# PIC32_Circuit.net
KiCad netlist of a schematic drawn in EAGLE
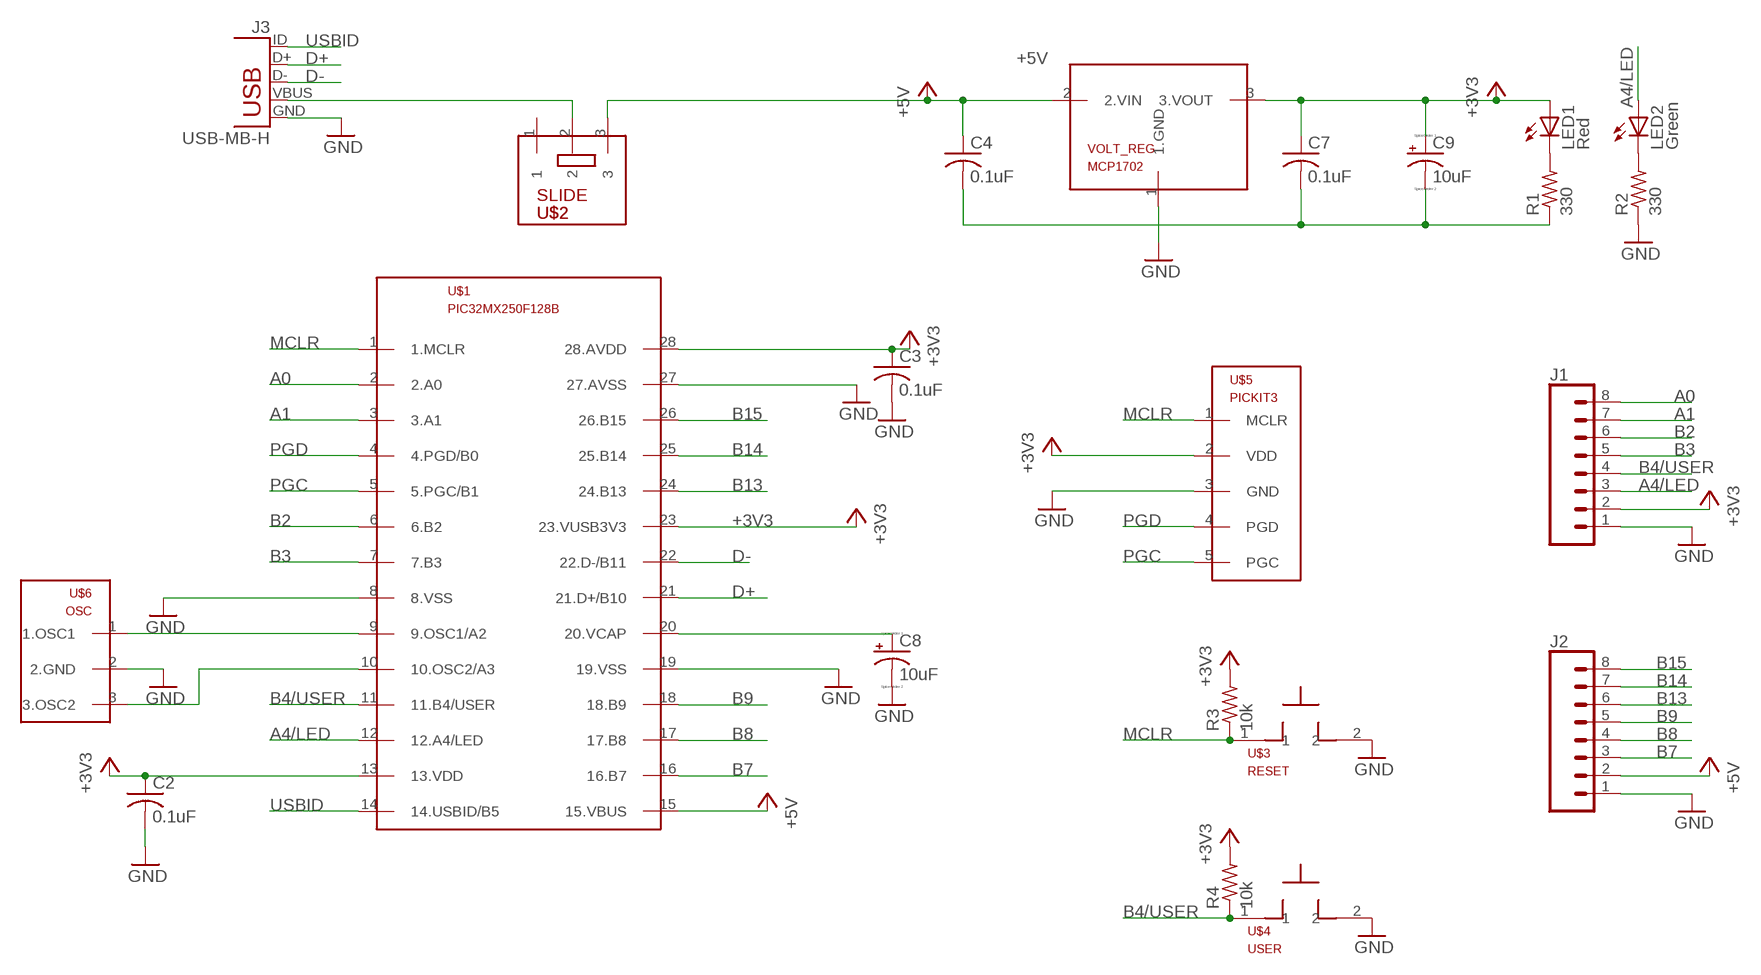
[diagram p0: schematic, sheet 1]

(export (version "E")
  (design (tool "Eeschema 10.0.6"))
  (components
    (comp (ref "C2")
      (value "0.1uF")
      (footprint "eagle-import:C025-050X050")
      (libsource (lib "eagle-import") (part "C-US025-050X050"))
    )
    (comp (ref "C3")
      (value "0.1uF")
      (footprint "eagle-import:C025-050X050")
      (libsource (lib "eagle-import") (part "C-US025-050X050"))
    )
    (comp (ref "C4")
      (value "0.1uF")
      (footprint "eagle-import:C025-050X050")
      (libsource (lib "eagle-import") (part "C-US025-050X050"))
    )
    (comp (ref "C7")
      (value "0.1uF")
      (footprint "eagle-import:C025-050X050")
      (libsource (lib "eagle-import") (part "C-US025-050X050"))
    )
    (comp (ref "C8")
      (value "10uF")
      (footprint "eagle-import:B45181B")
      (libsource (lib "eagle-import") (part "CPOL-USB45181B"))
    )
    (comp (ref "C9")
      (value "10uF")
      (footprint "eagle-import:B45181B")
      (libsource (lib "eagle-import") (part "CPOL-USB45181B"))
    )
    (comp (ref "J1")
      (value "CONN_08\"")
      (footprint "eagle-import:1X08")
      (libsource (lib "eagle-import") (part "CONN_08{dblquote}"))
    )
    (comp (ref "J2")
      (value "CONN_08\"")
      (footprint "eagle-import:1X08")
      (libsource (lib "eagle-import") (part "CONN_08{dblquote}"))
    )
    (comp (ref "J3")
      (value "USB-MB-H")
      (footprint "eagle-import:USB-MB-H")
      (libsource (lib "eagle-import") (part "USB-MB-H"))
    )
    (comp (ref "LED1")
      (value "Red")
      (footprint "eagle-import:LED3MM")
      (libsource (lib "eagle-import") (part "led_LED3MM"))
    )
    (comp (ref "LED2")
      (value "Green")
      (footprint "eagle-import:LED3MM")
      (libsource (lib "eagle-import") (part "LED3MM"))
    )
    (comp (ref "R1")
      (value "330")
      (footprint "eagle-import:0309_12")
      (libsource (lib "eagle-import") (part "resistor_R-US_0309/12"))
    )
    (comp (ref "R2")
      (value "330")
      (footprint "eagle-import:0207_10")
      (libsource (lib "eagle-import") (part "R-US_0207/10"))
    )
    (comp (ref "R3")
      (value "10k")
      (footprint "eagle-import:0207_10")
      (libsource (lib "eagle-import") (part "R-US_0207/10"))
    )
    (comp (ref "R4")
      (value "10k")
      (footprint "eagle-import:0207_10")
      (libsource (lib "eagle-import") (part "R-US_0207/10"))
    )
    (comp (ref "U$1")
      (value "PIC32MX250F128B")
      (footprint "eagle-import:DIL28-3")
      (libsource (lib "eagle-import") (part "PIC32MX250F128B"))
    )
    (comp (ref "U$2")
      (value "SLIDE")
      (footprint "eagle-import:SLIDE")
      (libsource (lib "eagle-import") (part "SLIDE"))
    )
    (comp (ref "U$3")
      (value "RESET")
      (footprint "eagle-import:PB")
      (libsource (lib "eagle-import") (part "PB"))
    )
    (comp (ref "U$4")
      (value "USER")
      (footprint "eagle-import:PB")
      (libsource (lib "eagle-import") (part "PB"))
    )
    (comp (ref "U$5")
      (value "PICKIT3")
      (footprint "eagle-import:1X05")
      (libsource (lib "eagle-import") (part "PICKIT3"))
    )
    (comp (ref "U$6")
      (value "OSC")
      (footprint "eagle-import:OSC")
      (libsource (lib "eagle-import") (part "OSC"))
    )
    (comp (ref "VOLT_REG")
      (value "MCP1702")
      (footprint "eagle-import:TO92")
      (libsource (lib "eagle-import") (part "MCP1702"))
    )
  )
  (nets
    (net (code "1") (name "+3V3") (class "Default")
      (node (ref "C2") (pin "1") (pinfunction "1_1") (pintype "passive"))
      (node (ref "C3") (pin "1") (pinfunction "1_1") (pintype "passive"))
      (node (ref "C7") (pin "1") (pinfunction "1_1") (pintype "passive"))
      (node (ref "C9") (pin "+") (pinfunction "+_+") (pintype "passive"))
      (node (ref "J1") (pin "2") (pinfunction "2_2") (pintype "passive"))
      (node (ref "LED1") (pin "A") (pinfunction "A_A") (pintype "passive"))
      (node (ref "R3") (pin "2") (pinfunction "2_2") (pintype "passive"))
      (node (ref "R4") (pin "2") (pinfunction "2_2") (pintype "passive"))
      (node (ref "U$1") (pin "13") (pinfunction "13.VDD_13") (pintype "bidirectional"))
      (node (ref "U$1") (pin "23") (pinfunction "23.VUSB3V3_23") (pintype "bidirectional"))
      (node (ref "U$1") (pin "28") (pinfunction "28.AVDD_28") (pintype "bidirectional"))
      (node (ref "U$5") (pin "2") (pinfunction "VDD_2") (pintype "bidirectional"))
      (node (ref "VOLT_REG") (pin "3") (pinfunction "3.VOUT_3") (pintype "bidirectional"))
    )
    (net (code "2") (name "+5V") (class "Default")
      (node (ref "C4") (pin "1") (pinfunction "1_1") (pintype "passive"))
      (node (ref "J2") (pin "2") (pinfunction "2_2") (pintype "passive"))
      (node (ref "U$1") (pin "15") (pinfunction "15.VBUS_15") (pintype "bidirectional"))
      (node (ref "U$2") (pin "3") (pinfunction "3_3") (pintype "bidirectional"))
      (node (ref "VOLT_REG") (pin "2") (pinfunction "2.VIN_2") (pintype "bidirectional"))
    )
    (net (code "3") (name "/A0") (class "Default")
      (node (ref "J1") (pin "8") (pinfunction "8_8") (pintype "passive"))
      (node (ref "U$1") (pin "2") (pinfunction "2.A0_2") (pintype "bidirectional"))
    )
    (net (code "4") (name "/A1") (class "Default")
      (node (ref "J1") (pin "7") (pinfunction "7_7") (pintype "passive"))
      (node (ref "U$1") (pin "3") (pinfunction "3.A1_3") (pintype "bidirectional"))
    )
    (net (code "5") (name "/A4{slash}LED") (class "Default")
      (node (ref "J1") (pin "3") (pinfunction "3_3") (pintype "passive"))
      (node (ref "LED2") (pin "A") (pinfunction "A_A") (pintype "passive"))
      (node (ref "U$1") (pin "12") (pinfunction "12.A4/LED_12") (pintype "bidirectional"))
    )
    (net (code "6") (name "/B2") (class "Default")
      (node (ref "J1") (pin "6") (pinfunction "6_6") (pintype "passive"))
      (node (ref "U$1") (pin "6") (pinfunction "6.B2_6") (pintype "bidirectional"))
    )
    (net (code "7") (name "/B3") (class "Default")
      (node (ref "J1") (pin "5") (pinfunction "5_5") (pintype "passive"))
      (node (ref "U$1") (pin "7") (pinfunction "7.B3_7") (pintype "bidirectional"))
    )
    (net (code "8") (name "/B4{slash}USER") (class "Default")
      (node (ref "J1") (pin "4") (pinfunction "4_4") (pintype "passive"))
      (node (ref "R4") (pin "1") (pinfunction "1_1") (pintype "passive"))
      (node (ref "U$1") (pin "11") (pinfunction "11.B4/USER_11") (pintype "bidirectional"))
      (node (ref "U$4") (pin "1") (pinfunction "1_1") (pintype "bidirectional"))
    )
    (net (code "9") (name "/B7") (class "Default")
      (node (ref "J2") (pin "3") (pinfunction "3_3") (pintype "passive"))
      (node (ref "U$1") (pin "16") (pinfunction "16.B7_16") (pintype "bidirectional"))
    )
    (net (code "10") (name "/B8") (class "Default")
      (node (ref "J2") (pin "4") (pinfunction "4_4") (pintype "passive"))
      (node (ref "U$1") (pin "17") (pinfunction "17.B8_17") (pintype "bidirectional"))
    )
    (net (code "11") (name "/B9") (class "Default")
      (node (ref "J2") (pin "5") (pinfunction "5_5") (pintype "passive"))
      (node (ref "U$1") (pin "18") (pinfunction "18.B9_18") (pintype "bidirectional"))
    )
    (net (code "12") (name "/B13") (class "Default")
      (node (ref "J2") (pin "6") (pinfunction "6_6") (pintype "passive"))
      (node (ref "U$1") (pin "24") (pinfunction "24.B13_24") (pintype "bidirectional"))
    )
    (net (code "13") (name "/B14") (class "Default")
      (node (ref "J2") (pin "7") (pinfunction "7_7") (pintype "passive"))
      (node (ref "U$1") (pin "25") (pinfunction "25.B14_25") (pintype "bidirectional"))
    )
    (net (code "14") (name "/B15") (class "Default")
      (node (ref "J2") (pin "8") (pinfunction "8_8") (pintype "passive"))
      (node (ref "U$1") (pin "26") (pinfunction "26.B15_26") (pintype "bidirectional"))
    )
    (net (code "15") (name "/D+") (class "Default")
      (node (ref "J3") (pin "D+") (pinfunction "D+_D+") (pintype "bidirectional"))
      (node (ref "U$1") (pin "21") (pinfunction "21.D+/B10_21") (pintype "bidirectional"))
    )
    (net (code "16") (name "/D-") (class "Default")
      (node (ref "J3") (pin "D-") (pinfunction "D-_D-") (pintype "bidirectional"))
      (node (ref "U$1") (pin "22") (pinfunction "22.D-/B11_22") (pintype "bidirectional"))
    )
    (net (code "17") (name "/MCLR") (class "Default")
      (node (ref "R3") (pin "1") (pinfunction "1_1") (pintype "passive"))
      (node (ref "U$1") (pin "1") (pinfunction "1.MCLR_1") (pintype "bidirectional"))
      (node (ref "U$3") (pin "1") (pinfunction "1_1") (pintype "bidirectional"))
      (node (ref "U$5") (pin "1") (pinfunction "MCLR_1") (pintype "bidirectional"))
    )
    (net (code "18") (name "/PGC") (class "Default")
      (node (ref "U$1") (pin "5") (pinfunction "5.PGC/B1_5") (pintype "bidirectional"))
      (node (ref "U$5") (pin "5") (pinfunction "PGC_5") (pintype "bidirectional"))
    )
    (net (code "19") (name "/PGD") (class "Default")
      (node (ref "U$1") (pin "4") (pinfunction "4.PGD/B0_4") (pintype "bidirectional"))
      (node (ref "U$5") (pin "4") (pinfunction "PGD_4") (pintype "bidirectional"))
    )
    (net (code "20") (name "/USBID") (class "Default")
      (node (ref "J3") (pin "ID") (pinfunction "ID_ID") (pintype "bidirectional"))
      (node (ref "U$1") (pin "14") (pinfunction "14.USBID/B5_14") (pintype "bidirectional"))
    )
    (net (code "21") (name "GND") (class "Default")
      (node (ref "C2") (pin "2") (pinfunction "2_2") (pintype "passive"))
      (node (ref "C3") (pin "2") (pinfunction "2_2") (pintype "passive"))
      (node (ref "C8") (pin "-") (pinfunction "-_-") (pintype "passive"))
      (node (ref "J1") (pin "1") (pinfunction "1_1") (pintype "passive"))
      (node (ref "J2") (pin "1") (pinfunction "1_1") (pintype "passive"))
      (node (ref "J3") (pin "GND") (pinfunction "GND_GND") (pintype "bidirectional"))
      (node (ref "R2") (pin "1") (pinfunction "1_1") (pintype "passive"))
      (node (ref "U$1") (pin "19") (pinfunction "19.VSS_19") (pintype "bidirectional"))
      (node (ref "U$1") (pin "27") (pinfunction "27.AVSS_27") (pintype "bidirectional"))
      (node (ref "U$1") (pin "8") (pinfunction "8.VSS_8") (pintype "bidirectional"))
      (node (ref "U$3") (pin "2") (pinfunction "2_2") (pintype "bidirectional"))
      (node (ref "U$4") (pin "2") (pinfunction "2_2") (pintype "bidirectional"))
      (node (ref "U$5") (pin "3") (pinfunction "GND_3") (pintype "bidirectional"))
      (node (ref "U$6") (pin "2") (pinfunction "2.GND_2") (pintype "bidirectional"))
      (node (ref "VOLT_REG") (pin "1") (pinfunction "1.GND_1") (pintype "bidirectional"))
    )
    (net (code "22") (name "Net-(C4-Pad2)") (class "Default")
      (node (ref "C4") (pin "2") (pinfunction "2_2") (pintype "passive"))
      (node (ref "C7") (pin "2") (pinfunction "2_2") (pintype "passive"))
      (node (ref "C9") (pin "-") (pinfunction "-_-") (pintype "passive"))
      (node (ref "R1") (pin "1") (pinfunction "1_1") (pintype "passive"))
    )
    (net (code "23") (name "Net-(J3-PadVBUS)") (class "Default")
      (node (ref "J3") (pin "VBUS") (pinfunction "VBUS_VBUS") (pintype "bidirectional"))
      (node (ref "U$2") (pin "2") (pinfunction "2_2") (pintype "bidirectional"))
    )
    (net (code "24") (name "Net-(LED1-C)") (class "Default")
      (node (ref "LED1") (pin "K") (pinfunction "C_K") (pintype "passive"))
      (node (ref "R1") (pin "2") (pinfunction "2_2") (pintype "passive"))
    )
    (net (code "25") (name "Net-(LED2-C)") (class "Default")
      (node (ref "LED2") (pin "K") (pinfunction "C_K") (pintype "passive"))
      (node (ref "R2") (pin "2") (pinfunction "2_2") (pintype "passive"))
    )
    (net (code "26") (name "Net-(U$1-9.OSC1{slash}A2)") (class "Default")
      (node (ref "U$1") (pin "9") (pinfunction "9.OSC1/A2_9") (pintype "bidirectional"))
      (node (ref "U$6") (pin "1") (pinfunction "1.OSC1_1") (pintype "bidirectional"))
    )
    (net (code "27") (name "Net-(U$1-10.OSC2{slash}A3)") (class "Default")
      (node (ref "U$1") (pin "10") (pinfunction "10.OSC2/A3_10") (pintype "bidirectional"))
      (node (ref "U$6") (pin "3") (pinfunction "3.OSC2_3") (pintype "bidirectional"))
    )
    (net (code "28") (name "Net-(U$1-20.VCAP)") (class "Default")
      (node (ref "C8") (pin "+") (pinfunction "+_+") (pintype "passive"))
      (node (ref "U$1") (pin "20") (pinfunction "20.VCAP_20") (pintype "bidirectional"))
    )
    (net (code "29") (name "unconnected-(U$2-Pad1)") (class "Default")
      (node (ref "U$2") (pin "1") (pinfunction "1_1") (pintype "bidirectional"))
    )
  )
)
